# Radio1.net
KiCad netlist of a schematic drawn in Altium Designer
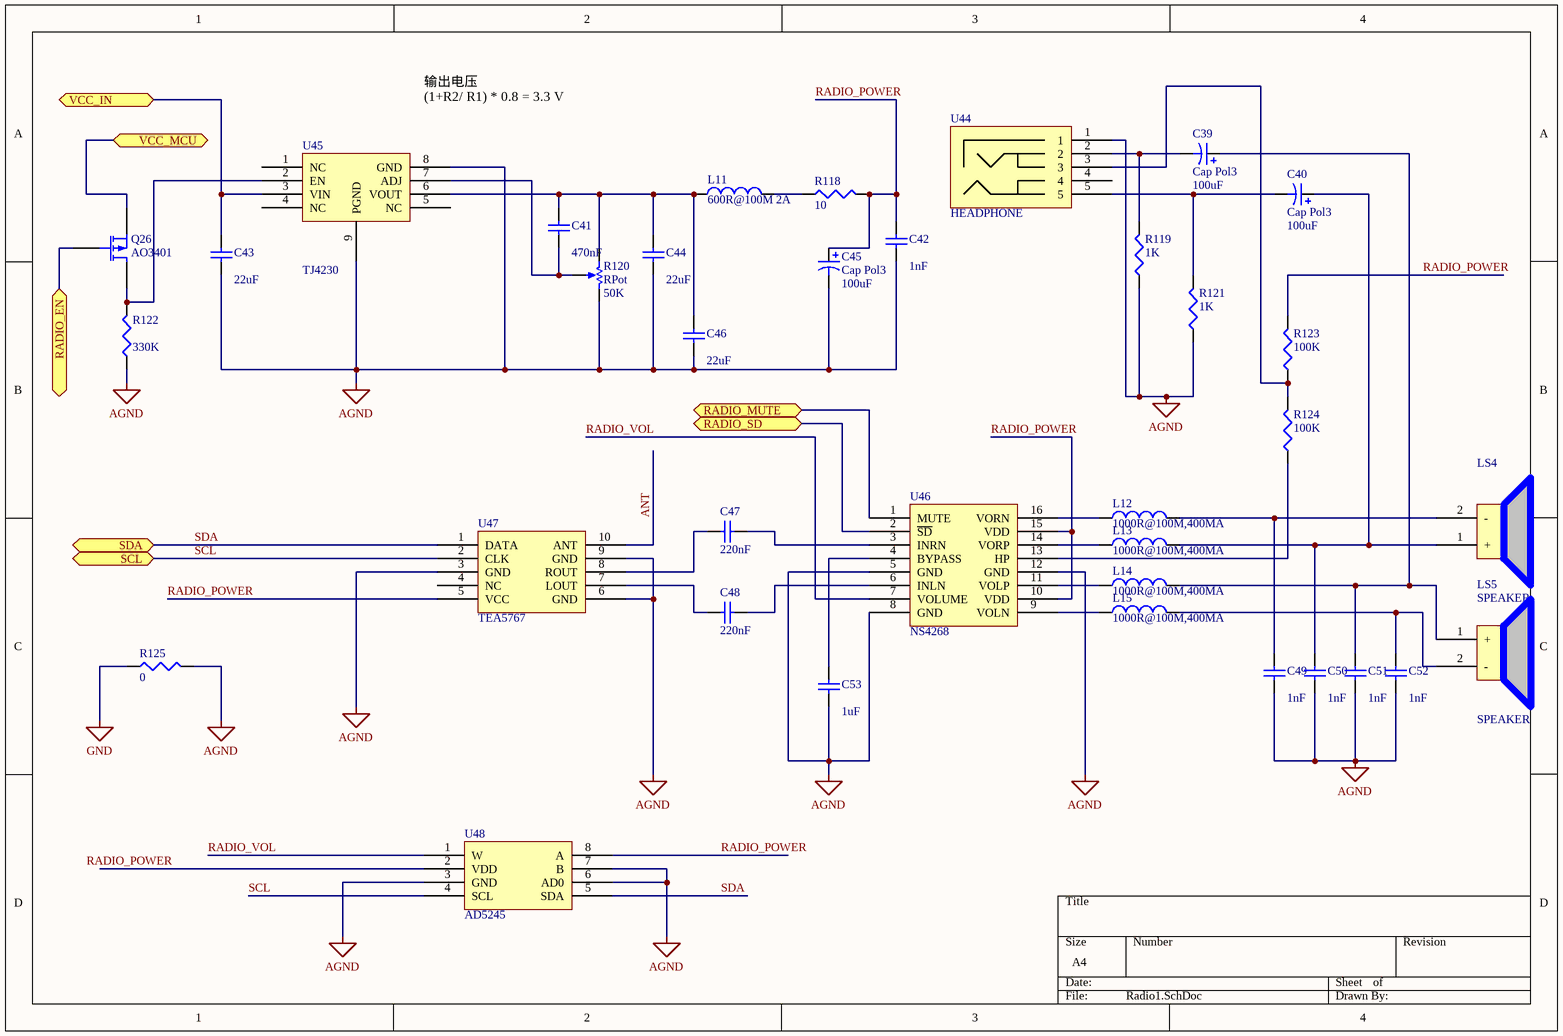
[diagram p0: Radio1.SchDoc]

(export (version "E")
  (design (tool "Eeschema 10.0.6"))
  (components
    (comp (ref "C39")
      (value "Cap Pol3")
      (footprint "clock:TC7343-2917")
      (description "Polarized Capacitor (Surface Mount)")
      (fields (field (name "ALTIUM_VALUE") "100uF") (field (name "PUBLISHER") "Altium Limited"))
      (libsource (lib "Miscellaneous Devices") (part "Cap Pol3"))
    )
    (comp (ref "C40")
      (value "Cap Pol3")
      (footprint "clock:TC7343-2917")
      (description "Polarized Capacitor (Surface Mount)")
      (fields (field (name "ALTIUM_VALUE") "100uF") (field (name "PUBLISHER") "Altium Limited"))
      (libsource (lib "Miscellaneous Devices") (part "Cap Pol3"))
    )
    (comp (ref "C41")
      (value "470nF")
      (footprint "clock:0603")
      (description "Capacitor (Semiconductor SIM Model)")
      (fields (field (name "Comment") "Cap Semi") (field (name "PUBLISHER") "Altium Limited"))
      (libsource (lib "Miscellaneous Devices") (part "Cap Semi"))
    )
    (comp (ref "C42")
      (value "1nF")
      (footprint "clock:0603")
      (description "Capacitor (Semiconductor SIM Model)")
      (fields (field (name "Comment") "Cap Semi") (field (name "PUBLISHER") "Altium Limited"))
      (libsource (lib "Miscellaneous Devices") (part "Cap Semi"))
    )
    (comp (ref "C43")
      (value "22uF")
      (footprint "clock:1206")
      (description "Capacitor (Semiconductor SIM Model)")
      (fields (field (name "Comment") "Cap Semi") (field (name "PUBLISHER") "Altium Limited"))
      (libsource (lib "Miscellaneous Devices") (part "Cap Semi"))
    )
    (comp (ref "C44")
      (value "22uF")
      (footprint "clock:1206")
      (description "Capacitor (Semiconductor SIM Model)")
      (fields (field (name "Comment") "Cap Semi") (field (name "PUBLISHER") "Altium Limited"))
      (libsource (lib "Miscellaneous Devices") (part "Cap Semi"))
    )
    (comp (ref "C45")
      (value "Cap Pol3")
      (footprint "clock:TC7343-2917")
      (description "Polarized Capacitor (Surface Mount)")
      (fields (field (name "ALTIUM_VALUE") "100uF") (field (name "PUBLISHER") "Altium Limited"))
      (libsource (lib "Miscellaneous Devices") (part "Cap Pol3"))
    )
    (comp (ref "C46")
      (value "22uF")
      (footprint "clock:1210")
      (description "Capacitor (Semiconductor SIM Model)")
      (fields (field (name "Comment") "Cap Semi") (field (name "PUBLISHER") "Altium Limited"))
      (libsource (lib "Miscellaneous Devices") (part "Cap Semi"))
    )
    (comp (ref "C47")
      (value "220nF")
      (footprint "clock:0603")
      (description "Capacitor (Semiconductor SIM Model)")
      (fields (field (name "Comment") "Cap Semi") (field (name "PUBLISHER") "Altium Limited"))
      (libsource (lib "Miscellaneous Devices") (part "Cap Semi"))
    )
    (comp (ref "C48")
      (value "220nF")
      (footprint "clock:0603")
      (description "Capacitor (Semiconductor SIM Model)")
      (fields (field (name "Comment") "Cap Semi") (field (name "PUBLISHER") "Altium Limited"))
      (libsource (lib "Miscellaneous Devices") (part "Cap Semi"))
    )
    (comp (ref "C49")
      (value "1nF")
      (footprint "clock:0603")
      (description "Capacitor (Semiconductor SIM Model)")
      (fields (field (name "Comment") "Cap Semi") (field (name "PUBLISHER") "Altium Limited"))
      (libsource (lib "Miscellaneous Devices") (part "Cap Semi"))
    )
    (comp (ref "C50")
      (value "1nF")
      (footprint "clock:0603")
      (description "Capacitor (Semiconductor SIM Model)")
      (fields (field (name "Comment") "Cap Semi") (field (name "PUBLISHER") "Altium Limited"))
      (libsource (lib "Miscellaneous Devices") (part "Cap Semi"))
    )
    (comp (ref "C51")
      (value "1nF")
      (footprint "clock:0603")
      (description "Capacitor (Semiconductor SIM Model)")
      (fields (field (name "Comment") "Cap Semi") (field (name "PUBLISHER") "Altium Limited"))
      (libsource (lib "Miscellaneous Devices") (part "Cap Semi"))
    )
    (comp (ref "C52")
      (value "1nF")
      (footprint "clock:0603")
      (description "Capacitor (Semiconductor SIM Model)")
      (fields (field (name "Comment") "Cap Semi") (field (name "PUBLISHER") "Altium Limited"))
      (libsource (lib "Miscellaneous Devices") (part "Cap Semi"))
    )
    (comp (ref "C53")
      (value "1uF")
      (footprint "clock:0603")
      (description "Capacitor (Semiconductor SIM Model)")
      (fields (field (name "Comment") "Cap Semi") (field (name "PUBLISHER") "Altium Limited"))
      (libsource (lib "Miscellaneous Devices") (part "Cap Semi"))
    )
    (comp (ref "L11")
      (value "600R@100M 2A")
      (footprint "clock:AXIAL-0.6")
      (description "Inductor")
      (fields (field (name "PUBLISHER") "Altium Limited"))
      (libsource (lib "Miscellaneous Devices") (part "Inductor"))
    )
    (comp (ref "L12")
      (value "1000R@100M,400MA")
      (footprint "clock:0805")
      (description "Inductor")
      (fields (field (name "PUBLISHER") "Altium Limited"))
      (libsource (lib "Miscellaneous Devices") (part "Inductor"))
    )
    (comp (ref "L13")
      (value "1000R@100M,400MA")
      (footprint "clock:0805")
      (description "Inductor")
      (fields (field (name "PUBLISHER") "Altium Limited"))
      (libsource (lib "Miscellaneous Devices") (part "Inductor"))
    )
    (comp (ref "L14")
      (value "1000R@100M,400MA")
      (footprint "clock:0805")
      (description "Inductor")
      (fields (field (name "PUBLISHER") "Altium Limited"))
      (libsource (lib "Miscellaneous Devices") (part "Inductor"))
    )
    (comp (ref "L15")
      (value "1000R@100M,400MA")
      (footprint "clock:0805")
      (description "Inductor")
      (fields (field (name "PUBLISHER") "Altium Limited"))
      (libsource (lib "Miscellaneous Devices") (part "Inductor"))
    )
    (comp (ref "LS4")
      (value "SPEAKER")
      (footprint "clock:SPEAKER")
      (libsource (lib "clock") (part "SPEAKER"))
    )
    (comp (ref "LS5") (value "SPEAKER") (footprint "clock:SPEAKER") (libsource (lib "") (part "SPEAKER_1")))
    (comp (ref "Q26")
      (value "AO3401")
      (footprint "clock:SOT23-3-PMOS")
      (description "P-Channel MOSFET")
      (fields (field (name "PUBLISHER") "Altium Limited"))
      (libsource (lib "Miscellaneous Devices") (part "MOSFET-P"))
    )
    (comp (ref "R118")
      (value "10")
      (footprint "clock:0603")
      (description "Resistor")
      (fields (field (name "Comment") "Res3") (field (name "PUBLISHER") "Altium Limited"))
      (libsource (lib "Miscellaneous Devices") (part "Res3"))
    )
    (comp (ref "R119")
      (value "1K")
      (footprint "clock:0603")
      (description "Resistor")
      (fields (field (name "Comment") "Res3") (field (name "PUBLISHER") "Altium Limited"))
      (libsource (lib "Miscellaneous Devices") (part "Res3"))
    )
    (comp (ref "R120")
      (value "RPot")
      (footprint "clock:VR5")
      (description "Potentiometer")
      (fields (field (name "ALTIUM_VALUE") "50K") (field (name "PUBLISHER") "Altium Limited"))
      (libsource (lib "Miscellaneous Devices") (part "RPot"))
    )
    (comp (ref "R121")
      (value "1K")
      (footprint "clock:0603")
      (description "Resistor")
      (fields (field (name "Comment") "Res3") (field (name "PUBLISHER") "Altium Limited"))
      (libsource (lib "Miscellaneous Devices") (part "Res3"))
    )
    (comp (ref "R122")
      (value "330K")
      (footprint "clock:0603")
      (description "Resistor")
      (fields (field (name "Comment") "Res3") (field (name "PUBLISHER") "Altium Limited"))
      (libsource (lib "Miscellaneous Devices") (part "Res3"))
    )
    (comp (ref "R123")
      (value "100K")
      (footprint "clock:0603")
      (description "Resistor")
      (fields (field (name "Comment") "Res3") (field (name "PUBLISHER") "Altium Limited"))
      (libsource (lib "Miscellaneous Devices") (part "Res3"))
    )
    (comp (ref "R124")
      (value "100K")
      (footprint "clock:0603")
      (description "Resistor")
      (fields (field (name "Comment") "Res3") (field (name "PUBLISHER") "Altium Limited"))
      (libsource (lib "Miscellaneous Devices") (part "Res3"))
    )
    (comp (ref "R125")
      (value "0")
      (footprint "clock:0603")
      (description "Resistor")
      (fields (field (name "Comment") "Res3") (field (name "PUBLISHER") "Altium Limited"))
      (libsource (lib "Miscellaneous Devices") (part "Res3"))
    )
    (comp (ref "U44")
      (value "HEADPHONE")
      (footprint "clock:HEADPHONE")
      (libsource (lib "clock") (part "HEADPHONE"))
    )
    (comp (ref "U45") (value "TJ4230") (footprint "clock:SOP8-PAD") (libsource (lib "clock") (part "TJ4230")))
    (comp (ref "U46") (value "NS4268") (footprint "clock:SOP16") (libsource (lib "clock") (part "NS4268")))
    (comp (ref "U47")
      (value "TEA5767")
      (footprint "clock:TEA5767")
      (libsource (lib "clock") (part "TEA5767"))
    )
    (comp (ref "U48") (value "AD5245") (footprint "clock:SOT23-8") (libsource (lib "clock") (part "AD5245")))
  )
  (nets
    (net (code "1") (name "/ANT") (class "Default")
      (node (ref "U47") (pin "10") (pinfunction "ANT_10") (pintype "passive"))
    )
    (net (code "2") (name "/RADIO_EN") (class "Default")
      (node (ref "Q26") (pin "2") (pinfunction "G_2") (pintype "passive"))
    )
    (net (code "3") (name "/RADIO_MUTE") (class "Default")
      (node (ref "U46") (pin "1") (pinfunction "MUTE_1") (pintype "passive"))
    )
    (net (code "4") (name "/RADIO_POWER") (class "Default")
      (node (ref "C42") (pin "2") (pinfunction "2_2") (pintype "passive"))
      (node (ref "C45") (pin "1") (pinfunction "1_1") (pintype "passive"))
      (node (ref "R118") (pin "2") (pinfunction "2_2") (pintype "passive"))
      (node (ref "R123") (pin "2") (pinfunction "2_2") (pintype "passive"))
      (node (ref "U46") (pin "10") (pinfunction "VDD_10") (pintype "passive"))
      (node (ref "U46") (pin "15") (pinfunction "VDD_15") (pintype "passive"))
      (node (ref "U47") (pin "5") (pinfunction "VCC_5") (pintype "passive"))
      (node (ref "U48") (pin "8") (pinfunction "A_8") (pintype "passive"))
    )
    (net (code "5") (name "/RADIO_SD") (class "Default")
      (node (ref "U46") (pin "2") (pinfunction "~{SD}_2") (pintype "passive"))
    )
    (net (code "6") (name "/RADIO_VOL") (class "Default")
      (node (ref "U46") (pin "7") (pinfunction "VOLUME_7") (pintype "passive"))
      (node (ref "U48") (pin "1") (pinfunction "W_1") (pintype "passive"))
    )
    (net (code "7") (name "/SCL") (class "Default")
      (node (ref "U47") (pin "2") (pinfunction "CLK_2") (pintype "passive"))
      (node (ref "U48") (pin "4") (pinfunction "SCL_4") (pintype "passive"))
    )
    (net (code "8") (name "/SDA") (class "Default")
      (node (ref "U47") (pin "1") (pinfunction "DATA_1") (pintype "passive"))
      (node (ref "U48") (pin "5") (pinfunction "SDA_5") (pintype "passive"))
    )
    (net (code "9") (name "/VCC_IN") (class "Default")
      (node (ref "C43") (pin "2") (pinfunction "2_2") (pintype "passive"))
      (node (ref "U45") (pin "3") (pinfunction "VIN_3") (pintype "passive"))
    )
    (net (code "10") (name "/VCC_MCU") (class "Default")
      (node (ref "Q26") (pin "3") (pinfunction "S_3") (pintype "passive"))
    )
    (net (code "11") (name "AGND") (class "Default")
      (node (ref "C42") (pin "1") (pinfunction "1_1") (pintype "passive"))
      (node (ref "C43") (pin "1") (pinfunction "1_1") (pintype "passive"))
      (node (ref "C44") (pin "1") (pinfunction "1_1") (pintype "passive"))
      (node (ref "C45") (pin "2") (pinfunction "2_2") (pintype "passive"))
      (node (ref "C46") (pin "1") (pinfunction "1_1") (pintype "passive"))
      (node (ref "C49") (pin "1") (pinfunction "1_1") (pintype "passive"))
      (node (ref "C50") (pin "1") (pinfunction "1_1") (pintype "passive"))
      (node (ref "C51") (pin "1") (pinfunction "1_1") (pintype "passive"))
      (node (ref "C52") (pin "1") (pinfunction "1_1") (pintype "passive"))
      (node (ref "C53") (pin "1") (pinfunction "1_1") (pintype "passive"))
      (node (ref "R119") (pin "1") (pinfunction "1_1") (pintype "passive"))
      (node (ref "R120") (pin "1") (pinfunction "TOP_1") (pintype "passive"))
      (node (ref "R121") (pin "1") (pinfunction "1_1") (pintype "passive"))
      (node (ref "R122") (pin "1") (pinfunction "1_1") (pintype "passive"))
      (node (ref "R125") (pin "2") (pinfunction "2_2") (pintype "passive"))
      (node (ref "U44") (pin "1") (pinfunction "1_1") (pintype "passive"))
      (node (ref "U45") (pin "8") (pinfunction "GND_8") (pintype "passive"))
      (node (ref "U45") (pin "9") (pinfunction "PGND_9") (pintype "passive"))
      (node (ref "U46") (pin "12") (pinfunction "GND_12") (pintype "passive"))
      (node (ref "U46") (pin "5") (pinfunction "GND_5") (pintype "passive"))
      (node (ref "U46") (pin "8") (pinfunction "GND_8") (pintype "passive"))
      (node (ref "U47") (pin "3") (pinfunction "GND_3") (pintype "passive"))
      (node (ref "U47") (pin "6") (pinfunction "GND_6") (pintype "passive"))
      (node (ref "U47") (pin "9") (pinfunction "GND_9") (pintype "passive"))
      (node (ref "U48") (pin "3") (pinfunction "GND_3") (pintype "passive"))
      (node (ref "U48") (pin "6") (pinfunction "AD0_6") (pintype "passive"))
      (node (ref "U48") (pin "7") (pinfunction "B_7") (pintype "passive"))
    )
    (net (code "12") (name "GND") (class "Default")
      (node (ref "R125") (pin "1") (pinfunction "1_1") (pintype "passive"))
    )
    (net (code "13") (name "Net-(C39-Pad2)") (class "Default")
      (node (ref "C39") (pin "2") (pinfunction "2_2") (pintype "passive"))
      (node (ref "R119") (pin "2") (pinfunction "2_2") (pintype "passive"))
      (node (ref "U44") (pin "2") (pinfunction "2_2") (pintype "passive"))
    )
    (net (code "14") (name "Net-(C40-Pad2)") (class "Default")
      (node (ref "C40") (pin "2") (pinfunction "2_2") (pintype "passive"))
      (node (ref "R121") (pin "2") (pinfunction "2_2") (pintype "passive"))
      (node (ref "U44") (pin "5") (pinfunction "5_5") (pintype "passive"))
    )
    (net (code "15") (name "Net-(L11-Pad2)") (class "Default")
      (node (ref "L11") (pin "2") (pinfunction "2_2") (pintype "passive"))
      (node (ref "R118") (pin "1") (pinfunction "1_1") (pintype "passive"))
    )
    (net (code "16") (name "Net-(LS4-+)") (class "Default")
      (node (ref "C40") (pin "1") (pinfunction "1_1") (pintype "passive"))
      (node (ref "C50") (pin "2") (pinfunction "2_2") (pintype "passive"))
      (node (ref "L13") (pin "2") (pinfunction "2_2") (pintype "passive"))
      (node (ref "LS4") (pin "1") (pinfunction "+_1") (pintype "passive"))
    )
    (net (code "17") (name "Net-(LS4--)") (class "Default")
      (node (ref "C49") (pin "2") (pinfunction "2_2") (pintype "passive"))
      (node (ref "L12") (pin "2") (pinfunction "2_2") (pintype "passive"))
      (node (ref "LS4") (pin "2") (pinfunction "-_2") (pintype "passive"))
    )
    (net (code "18") (name "Net-(LS5-+)") (class "Default")
      (node (ref "C39") (pin "1") (pinfunction "1_1") (pintype "passive"))
      (node (ref "C51") (pin "2") (pinfunction "2_2") (pintype "passive"))
      (node (ref "L14") (pin "2") (pinfunction "2_2") (pintype "passive"))
      (node (ref "LS5") (pin "1") (pinfunction "+_1") (pintype "passive"))
    )
    (net (code "19") (name "Net-(LS5--)") (class "Default")
      (node (ref "C52") (pin "2") (pinfunction "2_2") (pintype "passive"))
      (node (ref "L15") (pin "2") (pinfunction "2_2") (pintype "passive"))
      (node (ref "LS5") (pin "2") (pinfunction "-_2") (pintype "passive"))
    )
    (net (code "20") (name "Net-(Q26-D)") (class "Default")
      (node (ref "Q26") (pin "1") (pinfunction "D_1") (pintype "passive"))
      (node (ref "R122") (pin "2") (pinfunction "2_2") (pintype "passive"))
      (node (ref "U45") (pin "2") (pinfunction "EN_2") (pintype "passive"))
    )
    (net (code "21") (name "Net-(R120-BOT)") (class "Default")
      (node (ref "C41") (pin "2") (pinfunction "2_2") (pintype "passive"))
      (node (ref "C44") (pin "2") (pinfunction "2_2") (pintype "passive"))
      (node (ref "C46") (pin "2") (pinfunction "2_2") (pintype "passive"))
      (node (ref "L11") (pin "1") (pinfunction "1_1") (pintype "passive"))
      (node (ref "R120") (pin "2") (pinfunction "BOT_2") (pintype "passive"))
      (node (ref "U45") (pin "6") (pinfunction "VOUT_6") (pintype "passive"))
    )
    (net (code "22") (name "Net-(R120-TAP)") (class "Default")
      (node (ref "C41") (pin "1") (pinfunction "1_1") (pintype "passive"))
      (node (ref "R120") (pin "3") (pinfunction "TAP_3") (pintype "passive"))
      (node (ref "U45") (pin "7") (pinfunction "ADJ_7") (pintype "passive"))
    )
    (net (code "23") (name "Net-(R123-Pad1)") (class "Default")
      (node (ref "R123") (pin "1") (pinfunction "1_1") (pintype "passive"))
      (node (ref "R124") (pin "2") (pinfunction "2_2") (pintype "passive"))
      (node (ref "U44") (pin "3") (pinfunction "3_3") (pintype "passive"))
    )
    (net (code "24") (name "Net-(U46-BYPASS)") (class "Default")
      (node (ref "C53") (pin "2") (pinfunction "2_2") (pintype "passive"))
      (node (ref "U46") (pin "4") (pinfunction "BYPASS_4") (pintype "passive"))
    )
    (net (code "25") (name "Net-(U46-HP)") (class "Default")
      (node (ref "R124") (pin "1") (pinfunction "1_1") (pintype "passive"))
      (node (ref "U46") (pin "13") (pinfunction "HP_13") (pintype "passive"))
    )
    (net (code "26") (name "Net-(U46-INLN)") (class "Default")
      (node (ref "C48") (pin "1") (pinfunction "1_1") (pintype "passive"))
      (node (ref "U46") (pin "6") (pinfunction "INLN_6") (pintype "passive"))
    )
    (net (code "27") (name "Net-(U46-INRN)") (class "Default")
      (node (ref "C47") (pin "1") (pinfunction "1_1") (pintype "passive"))
      (node (ref "U46") (pin "3") (pinfunction "INRN_3") (pintype "passive"))
    )
    (net (code "28") (name "Net-(U46-VOLN)") (class "Default")
      (node (ref "L15") (pin "1") (pinfunction "1_1") (pintype "passive"))
      (node (ref "U46") (pin "9") (pinfunction "VOLN_9") (pintype "passive"))
    )
    (net (code "29") (name "Net-(U46-VOLP)") (class "Default")
      (node (ref "L14") (pin "1") (pinfunction "1_1") (pintype "passive"))
      (node (ref "U46") (pin "11") (pinfunction "VOLP_11") (pintype "passive"))
    )
    (net (code "30") (name "Net-(U46-VORN)") (class "Default")
      (node (ref "L12") (pin "1") (pinfunction "1_1") (pintype "passive"))
      (node (ref "U46") (pin "16") (pinfunction "VORN_16") (pintype "passive"))
    )
    (net (code "31") (name "Net-(U46-VORP)") (class "Default")
      (node (ref "L13") (pin "1") (pinfunction "1_1") (pintype "passive"))
      (node (ref "U46") (pin "14") (pinfunction "VORP_14") (pintype "passive"))
    )
    (net (code "32") (name "Net-(U47-LOUT)") (class "Default")
      (node (ref "C48") (pin "2") (pinfunction "2_2") (pintype "passive"))
      (node (ref "U47") (pin "7") (pinfunction "LOUT_7") (pintype "passive"))
    )
    (net (code "33") (name "Net-(U47-ROUT)") (class "Default")
      (node (ref "C47") (pin "2") (pinfunction "2_2") (pintype "passive"))
      (node (ref "U47") (pin "8") (pinfunction "ROUT_8") (pintype "passive"))
    )
    (net (code "34") (name "unconnected-(U44-Pad4)") (class "Default")
      (node (ref "U44") (pin "4") (pinfunction "4_4") (pintype "passive"))
    )
    (net (code "35") (name "unconnected-(U45-NC-Pad1)") (class "Default")
      (node (ref "U45") (pin "1") (pinfunction "NC_1") (pintype "passive"))
    )
    (net (code "36") (name "unconnected-(U45-NC-Pad4)") (class "Default")
      (node (ref "U45") (pin "4") (pinfunction "NC_4") (pintype "passive"))
    )
    (net (code "37") (name "unconnected-(U45-NC-Pad5)") (class "Default")
      (node (ref "U45") (pin "5") (pinfunction "NC_5") (pintype "passive"))
    )
    (net (code "38") (name "unconnected-(U47-NC-Pad4)") (class "Default")
      (node (ref "U47") (pin "4") (pinfunction "NC_4") (pintype "passive"))
    )
    (net (code "39") (name "unconnected-(U48-VDD-Pad2)") (class "Default")
      (node (ref "U48") (pin "2") (pinfunction "VDD_2") (pintype "passive"))
    )
  )
)
